# greenhousectrl-latest.net
KiCad netlist of a schematic drawn in EAGLE
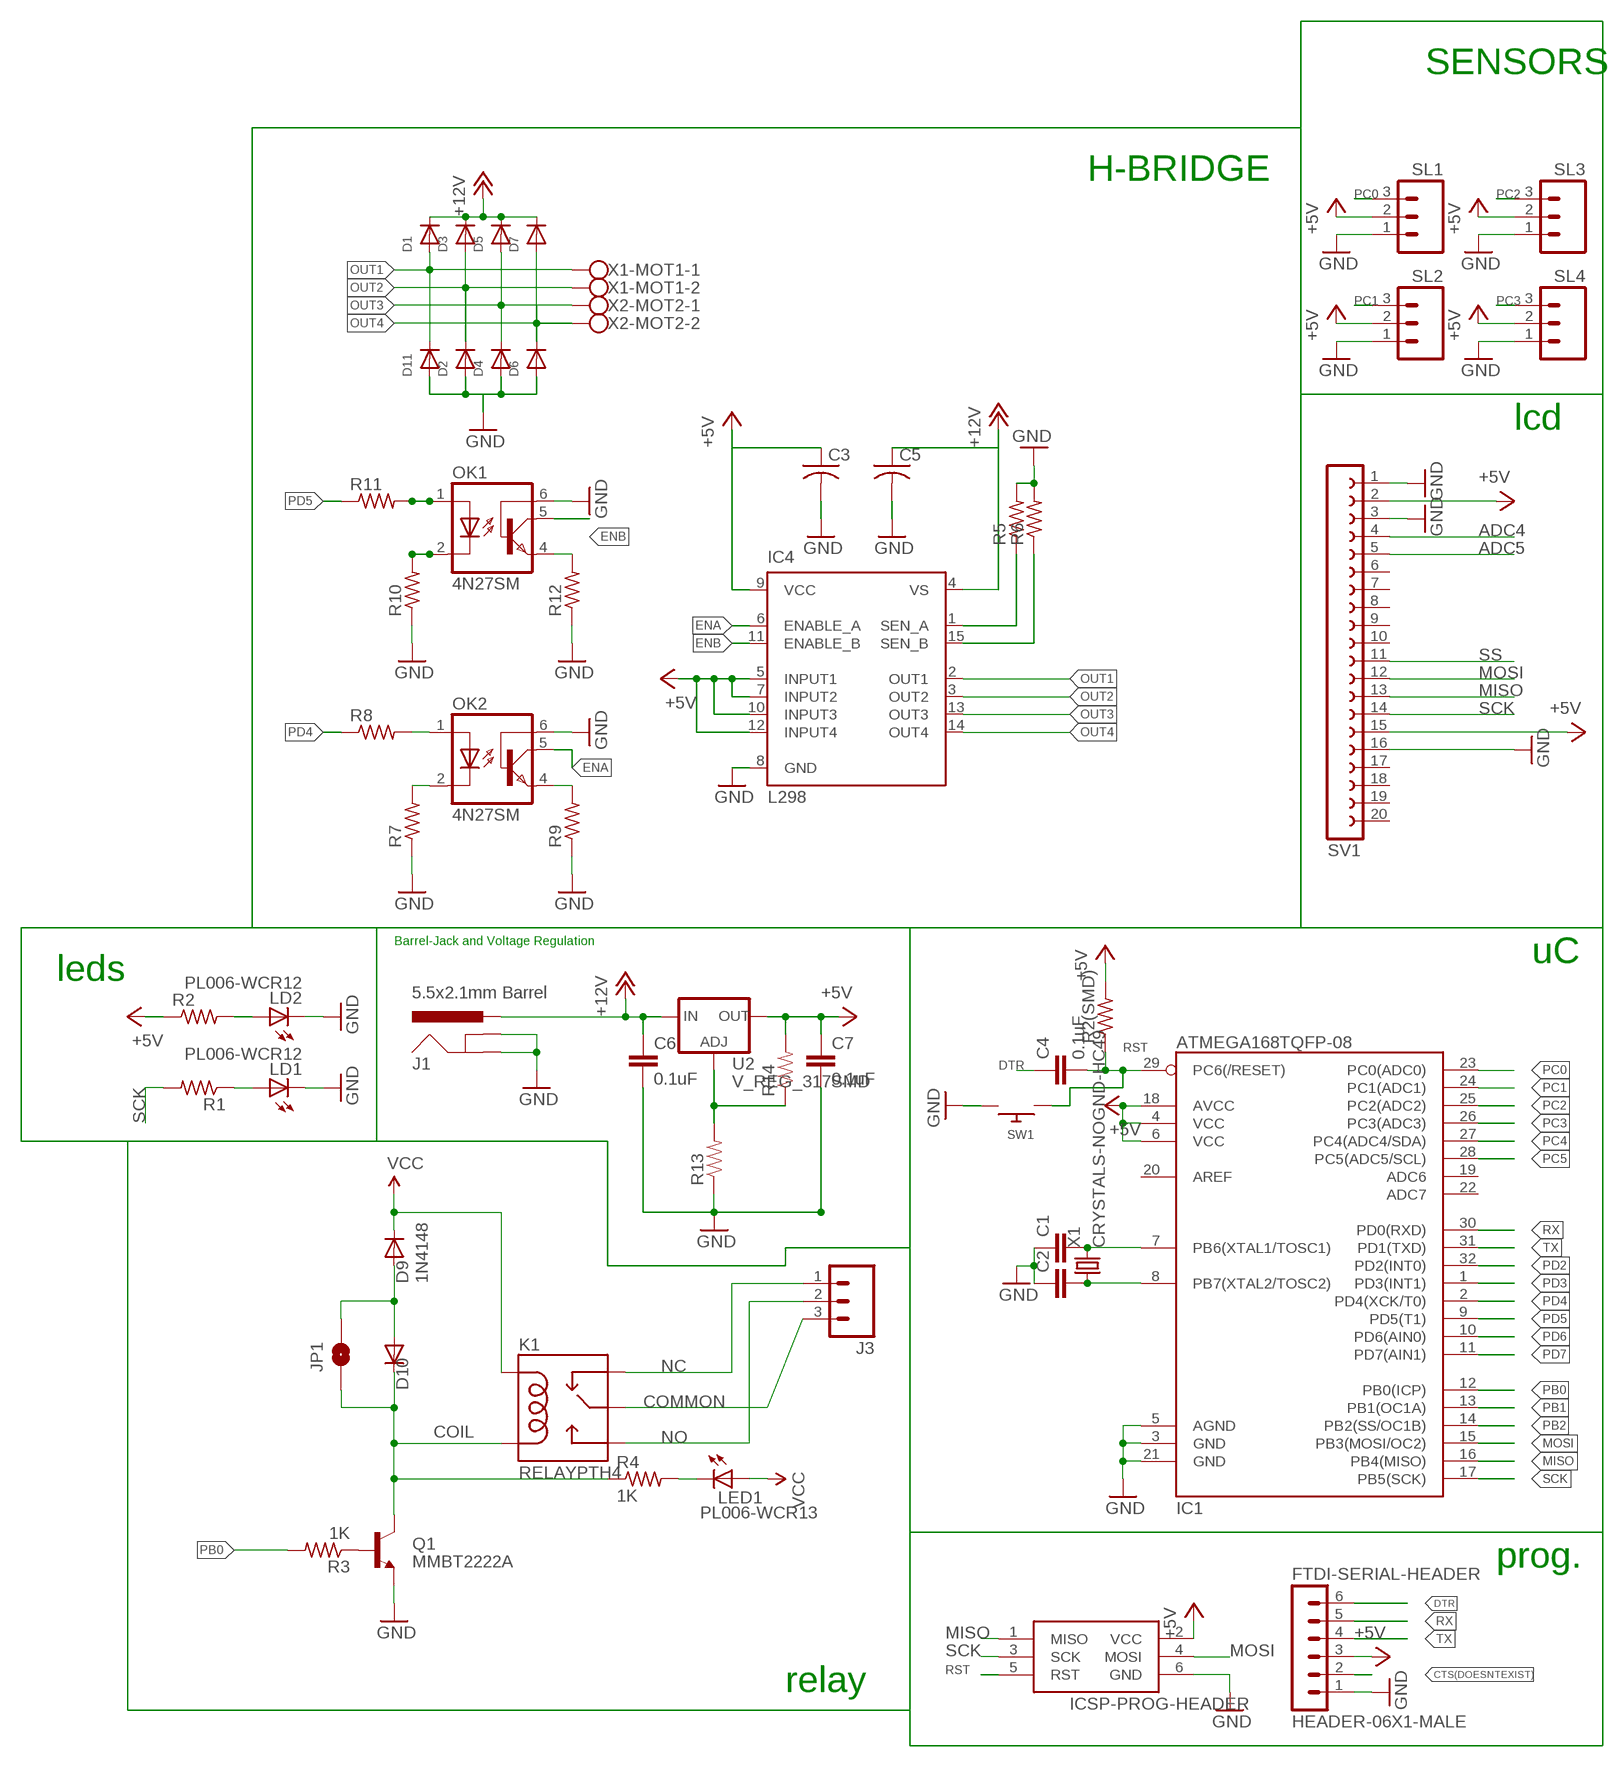
[diagram p0: schematic, sheet 1]

(export (version "E")
  (design (tool "Eeschema 10.0.6"))
  (components
    (comp (ref "C1")
      (value "C-EUC0805")
      (footprint "eagle-import:C0805")
      (libsource (lib "eagle-import") (part "C-EUC0805"))
    )
    (comp (ref "C2")
      (value "C-EUC0805")
      (footprint "eagle-import:C0805")
      (libsource (lib "eagle-import") (part "C-EUC0805"))
    )
    (comp (ref "C3")
      (value "C-US025-024X044")
      (footprint "eagle-import:C025-024X044")
      (libsource (lib "eagle-import") (part "C-US025-024X044"))
    )
    (comp (ref "C4")
      (value "0.1uF")
      (footprint "eagle-import:0603-CAP")
      (libsource (lib "eagle-import") (part "0.1UF-25V(+80/-20%)(0603)"))
    )
    (comp (ref "C5")
      (value "C-US025-024X044")
      (footprint "eagle-import:C025-024X044")
      (libsource (lib "eagle-import") (part "C-US025-024X044"))
    )
    (comp (ref "C6")
      (value "0.1uF")
      (footprint "eagle-import:0603-CAP")
      (libsource (lib "eagle-import") (part "0.1UF-25V(+80/-20%)(0603)"))
    )
    (comp (ref "C7")
      (value "0.1uF")
      (footprint "eagle-import:0603-CAP")
      (libsource (lib "eagle-import") (part "0.1UF-25V(+80/-20%)(0603)"))
    )
    (comp (ref "D1")
      (value "DIODESOD-523")
      (footprint "eagle-import:SOD-523")
      (libsource (lib "eagle-import") (part "DIODESOD-523"))
    )
    (comp (ref "D2")
      (value "DIODESOD-523")
      (footprint "eagle-import:SOD-523")
      (libsource (lib "eagle-import") (part "DIODESOD-523"))
    )
    (comp (ref "D3")
      (value "DIODESOD-523")
      (footprint "eagle-import:SOD-523")
      (libsource (lib "eagle-import") (part "DIODESOD-523"))
    )
    (comp (ref "D4")
      (value "DIODESOD-523")
      (footprint "eagle-import:SOD-523")
      (libsource (lib "eagle-import") (part "DIODESOD-523"))
    )
    (comp (ref "D5")
      (value "DIODESOD-523")
      (footprint "eagle-import:SOD-523")
      (libsource (lib "eagle-import") (part "DIODESOD-523"))
    )
    (comp (ref "D6")
      (value "DIODESOD-523")
      (footprint "eagle-import:SOD-523")
      (libsource (lib "eagle-import") (part "DIODESOD-523"))
    )
    (comp (ref "D7")
      (value "DIODESOD-523")
      (footprint "eagle-import:SOD-523")
      (libsource (lib "eagle-import") (part "DIODESOD-523"))
    )
    (comp (ref "D9")
      (value "1N4148")
      (footprint "eagle-import:SOD-323F")
      (libsource (lib "eagle-import") (part "DIODESOD-323F"))
    )
    (comp (ref "D10")
      (value "Zener")
      (footprint "eagle-import:SOD-323F")
      (libsource (lib "eagle-import") (part "DIODESOD-323F"))
    )
    (comp (ref "D11")
      (value "DIODESOD-523")
      (footprint "eagle-import:SOD-523")
      (libsource (lib "eagle-import") (part "DIODESOD-523"))
    )
    (comp (ref "FTDI-SERIAL-HEADER")
      (value "HEADER-06X1-MALE")
      (footprint "eagle-import:06X1-PTH")
      (libsource (lib "eagle-import") (part "HEADER-06X1?-MALE"))
    )
    (comp (ref "IC1")
      (value "ATMEGA168TQFP-08")
      (footprint "eagle-import:TQFP32-08")
      (libsource (lib "eagle-import") (part "ATMEGA168TQFP-08"))
    )
    (comp (ref "IC4")
      (value "L298")
      (footprint "eagle-import:MULTIWATT-15")
      (fields (field (name "MPN") "L298N"))
      (libsource (lib "eagle-import") (part "L298"))
    )
    (comp (ref "ICSP-PROG-HEADER")
      (value "AVRISP-6")
      (footprint "eagle-import:AVRISP")
      (libsource (lib "eagle-import") (part "AVRISP-6"))
    )
    (comp (ref "J1")
      (value "5.5x2.1mm Barrel")
      (footprint "eagle-import:POWER_JACK_SMD")
      (libsource (lib "eagle-import") (part "POWER_JACKSMD"))
    )
    (comp (ref "J3")
      (value "M03-SCREW-5MM")
      (footprint "eagle-import:SCREWTERMINAL-5MM-3")
      (libsource (lib "eagle-import") (part "M03-SCREW-5MM"))
    )
    (comp (ref "JP1")
      (value "JUMPER-PAD-2-NOYES_SILK")
      (footprint "eagle-import:PAD-JUMPER-2-NO_YES_SILK")
      (libsource (lib "eagle-import") (part "JUMPER-PAD-2-NOYES_SILK"))
    )
    (comp (ref "K1")
      (value "RELAYPTH4")
      (footprint "eagle-import:RELAY-JZC")
      (libsource (lib "eagle-import") (part "RELAYPTH4"))
    )
    (comp (ref "LD1")
      (value "PL006-WCR12")
      (footprint "eagle-import:SOT23")
      (libsource (lib "eagle-import") (part "PL006-WCR12"))
    )
    (comp (ref "LD2")
      (value "PL006-WCR12")
      (footprint "eagle-import:SOT23")
      (libsource (lib "eagle-import") (part "PL006-WCR12"))
    )
    (comp (ref "LED1")
      (value "PL006-WCR13")
      (footprint "eagle-import:SOT23")
      (fields (field (name "PROD_ID") "DIO-09529"))
      (libsource (lib "eagle-import") (part "PL006-WCR13"))
    )
    (comp (ref "OK1")
      (value "4N27SM")
      (footprint "eagle-import:DIL6-SMD")
      (fields (field (name "MF") "FAIRCHILD SEMICONDUCTOR") (field (name "MPN") "4N27S-M"))
      (libsource (lib "eagle-import") (part "4N?MS27"))
    )
    (comp (ref "OK2")
      (value "4N27SM")
      (footprint "eagle-import:DIL6-SMD")
      (fields (field (name "MF") "FAIRCHILD SEMICONDUCTOR") (field (name "MPN") "4N27S-M"))
      (libsource (lib "eagle-import") (part "4N?MS27"))
    )
    (comp (ref "Q1")
      (value "MMBT2222A")
      (footprint "eagle-import:SOT23-3")
      (libsource (lib "eagle-import") (part "TRANSISTOR_NPNMMBT2222A"))
    )
    (comp (ref "R1")
      (value "R-US_M0805")
      (footprint "eagle-import:M0805")
      (libsource (lib "eagle-import") (part "R-US_M0805"))
    )
    (comp (ref "R2")
      (value "R-US_M0805")
      (footprint "eagle-import:M0805")
      (libsource (lib "eagle-import") (part "R-US_M0805"))
    )
    (comp (ref "R2(SMD)")
      (value "R-US_M0805")
      (footprint "eagle-import:M0805")
      (libsource (lib "eagle-import") (part "R-US_M0805"))
    )
    (comp (ref "R3")
      (value "1K")
      (footprint "eagle-import:M0805")
      (libsource (lib "eagle-import") (part "R-US_M0805"))
    )
    (comp (ref "R4")
      (value "1K")
      (footprint "eagle-import:M0805")
      (libsource (lib "eagle-import") (part "R-US_M0805"))
    )
    (comp (ref "R5")
      (value "R-US_M0805")
      (footprint "eagle-import:M0805")
      (libsource (lib "eagle-import") (part "R-US_M0805"))
    )
    (comp (ref "R6")
      (value "R-US_M0805")
      (footprint "eagle-import:M0805")
      (libsource (lib "eagle-import") (part "R-US_M0805"))
    )
    (comp (ref "R7")
      (value "R-US_M0805")
      (footprint "eagle-import:M0805")
      (libsource (lib "eagle-import") (part "R-US_M0805"))
    )
    (comp (ref "R8")
      (value "R-US_M0805")
      (footprint "eagle-import:M0805")
      (libsource (lib "eagle-import") (part "R-US_M0805"))
    )
    (comp (ref "R9")
      (value "R-US_M0805")
      (footprint "eagle-import:M0805")
      (libsource (lib "eagle-import") (part "R-US_M0805"))
    )
    (comp (ref "R10")
      (value "R-US_M0805")
      (footprint "eagle-import:M0805")
      (libsource (lib "eagle-import") (part "R-US_M0805"))
    )
    (comp (ref "R11")
      (value "R-US_M0805")
      (footprint "eagle-import:M0805")
      (libsource (lib "eagle-import") (part "R-US_M0805"))
    )
    (comp (ref "R12")
      (value "R-US_M0805")
      (footprint "eagle-import:M0805")
      (libsource (lib "eagle-import") (part "R-US_M0805"))
    )
    (comp (ref "R13")
      (value "RESISTOR0402")
      (footprint "eagle-import:0402-RES")
      (libsource (lib "eagle-import") (part "RESISTOR0402"))
    )
    (comp (ref "R14")
      (value "RESISTOR0402")
      (footprint "eagle-import:0402-RES")
      (libsource (lib "eagle-import") (part "RESISTOR0402"))
    )
    (comp (ref "SL1")
      (value "M03")
      (footprint "eagle-import:03P")
      (libsource (lib "eagle-import") (part "M03"))
    )
    (comp (ref "SL2")
      (value "M03")
      (footprint "eagle-import:03P")
      (libsource (lib "eagle-import") (part "M03"))
    )
    (comp (ref "SL3")
      (value "M03")
      (footprint "eagle-import:03P")
      (libsource (lib "eagle-import") (part "M03"))
    )
    (comp (ref "SL4")
      (value "M03")
      (footprint "eagle-import:03P")
      (libsource (lib "eagle-import") (part "M03"))
    )
    (comp (ref "SV1")
      (value "FE20-1")
      (footprint "eagle-import:FE20")
      (libsource (lib "eagle-import") (part "FE20-1"))
    )
    (comp (ref "SW1")
      (value "SWITCH_PUSHBUTTONC&K_KSS")
      (footprint "eagle-import:BTN_CK_KSS")
      (libsource (lib "eagle-import") (part "SWITCH_PUSHBUTTONC&K_KSS"))
    )
    (comp (ref "U2")
      (value "V_REG_317SMD")
      (footprint "eagle-import:SOT223")
      (libsource (lib "eagle-import") (part "V_REG_317SMD"))
    )
    (comp (ref "X1")
      (value "CRYSTALS-NOGND-HC49")
      (footprint "eagle-import:HC49")
      (libsource (lib "eagle-import") (part "CRYSTALS-NOGND-HC49"))
    )
    (comp (ref "X1-MOT1")
      (value "W237-102")
      (footprint "eagle-import:W237-102")
      (fields (field (name "MPN") "237-102"))
      (libsource (lib "eagle-import") (part "W237-102"))
    )
    (comp (ref "X2-MOT2")
      (value "W237-102")
      (footprint "eagle-import:W237-102")
      (fields (field (name "MPN") "237-102"))
      (libsource (lib "eagle-import") (part "W237-102"))
    )
  )
  (nets
    (net (code "1") (name "+5V") (class "Default")
      (node (ref "C3") (pin "1") (pinfunction "1_1") (pintype "passive"))
      (node (ref "C7") (pin "1") (pinfunction "1_1") (pintype "passive"))
      (node (ref "FTDI-SERIAL-HEADER") (pin "3") (pinfunction "3_3") (pintype "passive"))
      (node (ref "IC1") (pin "18") (pinfunction "AVCC_18") (pintype "bidirectional"))
      (node (ref "IC1") (pin "4") (pinfunction "VCC_4") (pintype "bidirectional"))
      (node (ref "IC1") (pin "6") (pinfunction "VCC_6") (pintype "bidirectional"))
      (node (ref "IC4") (pin "10") (pinfunction "INPUT3_10") (pintype "input"))
      (node (ref "IC4") (pin "12") (pinfunction "INPUT4_12") (pintype "input"))
      (node (ref "IC4") (pin "5") (pinfunction "INPUT1_5") (pintype "input"))
      (node (ref "IC4") (pin "7") (pinfunction "INPUT2_7") (pintype "input"))
      (node (ref "IC4") (pin "9") (pinfunction "VCC_9") (pintype "power_in"))
      (node (ref "ICSP-PROG-HEADER") (pin "2") (pinfunction "VCC_2") (pintype "power_in"))
      (node (ref "R14") (pin "2") (pinfunction "2_2") (pintype "passive"))
      (node (ref "R2") (pin "1") (pinfunction "1_1") (pintype "passive"))
      (node (ref "R2(SMD)") (pin "2") (pinfunction "2_2") (pintype "passive"))
      (node (ref "SL1") (pin "2") (pinfunction "2_2") (pintype "passive"))
      (node (ref "SL2") (pin "2") (pinfunction "2_2") (pintype "passive"))
      (node (ref "SL3") (pin "2") (pinfunction "2_2") (pintype "passive"))
      (node (ref "SL4") (pin "2") (pinfunction "2_2") (pintype "passive"))
      (node (ref "SV1") (pin "15") (pinfunction "15_15") (pintype "passive"))
      (node (ref "SV1") (pin "2") (pinfunction "2_2") (pintype "passive"))
      (node (ref "U2") (pin "2") (pinfunction "OUT_2") (pintype "output"))
    )
    (net (code "2") (name "+12V") (class "Default")
      (node (ref "C5") (pin "1") (pinfunction "1_1") (pintype "passive"))
      (node (ref "C6") (pin "1") (pinfunction "1_1") (pintype "passive"))
      (node (ref "D1") (pin "K") (pinfunction "C_K") (pintype "passive"))
      (node (ref "D3") (pin "K") (pinfunction "C_K") (pintype "passive"))
      (node (ref "D5") (pin "K") (pinfunction "C_K") (pintype "passive"))
      (node (ref "D7") (pin "K") (pinfunction "C_K") (pintype "passive"))
      (node (ref "IC4") (pin "4") (pinfunction "VS_4") (pintype "power_in"))
      (node (ref "J1") (pin "VIN0") (pinfunction "PWR_VIN0") (pintype "bidirectional"))
      (node (ref "U2") (pin "3") (pinfunction "IN_3") (pintype "input"))
    )
    (net (code "3") (name "/ADC4") (class "Default")
      (node (ref "SV1") (pin "4") (pinfunction "4_4") (pintype "passive"))
    )
    (net (code "4") (name "/ADC5") (class "Default")
      (node (ref "SV1") (pin "5") (pinfunction "5_5") (pintype "passive"))
    )
    (net (code "5") (name "/COIL") (class "Default")
      (node (ref "D10") (pin "C") (pinfunction "C_C") (pintype "passive"))
      (node (ref "JP1") (pin "1") (pinfunction "1_1") (pintype "passive"))
      (node (ref "K1") (pin "1") (pinfunction "COIL2_1") (pintype "bidirectional"))
      (node (ref "Q1") (pin "3") (pinfunction "C_3") (pintype "passive"))
      (node (ref "R4") (pin "1") (pinfunction "1_1") (pintype "passive"))
    )
    (net (code "6") (name "/COMMON") (class "Default")
      (node (ref "J3") (pin "3") (pinfunction "3_3") (pintype "passive"))
      (node (ref "K1") (pin "4") (pinfunction "MAIN_4") (pintype "bidirectional"))
    )
    (net (code "7") (name "/NC") (class "Default")
      (node (ref "J3") (pin "1") (pinfunction "1_1") (pintype "passive"))
      (node (ref "K1") (pin "2") (pinfunction "NC_2") (pintype "bidirectional"))
    )
    (net (code "8") (name "/NO") (class "Default")
      (node (ref "J3") (pin "2") (pinfunction "2_2") (pintype "passive"))
      (node (ref "K1") (pin "3") (pinfunction "NO_3") (pintype "bidirectional"))
    )
    (net (code "9") (name "/RST") (class "Default")
      (node (ref "C4") (pin "2") (pinfunction "2_2") (pintype "passive"))
      (node (ref "IC1") (pin "29") (pinfunction "PC6(/RESET)_29") (pintype "bidirectional"))
      (node (ref "ICSP-PROG-HEADER") (pin "5") (pinfunction "RST_5") (pintype "output"))
      (node (ref "R2(SMD)") (pin "1") (pinfunction "1_1") (pintype "passive"))
      (node (ref "SW1") (pin "P$1") (pinfunction "P$1_P$1") (pintype "passive"))
    )
    (net (code "10") (name "/SS") (class "Default")
      (node (ref "SV1") (pin "11") (pinfunction "11_11") (pintype "passive"))
    )
    (net (code "11") (name "CTS(DOESNTEXIST)") (class "Default")
      (node (ref "FTDI-SERIAL-HEADER") (pin "2") (pinfunction "2_2") (pintype "passive"))
    )
    (net (code "12") (name "DTR") (class "Default")
      (node (ref "C4") (pin "1") (pinfunction "1_1") (pintype "passive"))
      (node (ref "FTDI-SERIAL-HEADER") (pin "6") (pinfunction "6_6") (pintype "passive"))
    )
    (net (code "13") (name "ENA") (class "Default")
      (node (ref "IC4") (pin "6") (pinfunction "ENABLE_A_6") (pintype "input"))
      (node (ref "OK2") (pin "5") (pinfunction "COL_5") (pintype "passive"))
    )
    (net (code "14") (name "ENB") (class "Default")
      (node (ref "IC4") (pin "11") (pinfunction "ENABLE_B_11") (pintype "input"))
      (node (ref "OK1") (pin "5") (pinfunction "COL_5") (pintype "passive"))
    )
    (net (code "15") (name "GND") (class "Default")
      (node (ref "C1") (pin "1") (pinfunction "1_1") (pintype "passive"))
      (node (ref "C2") (pin "1") (pinfunction "1_1") (pintype "passive"))
      (node (ref "C3") (pin "2") (pinfunction "2_2") (pintype "passive"))
      (node (ref "C5") (pin "2") (pinfunction "2_2") (pintype "passive"))
      (node (ref "C6") (pin "2") (pinfunction "2_2") (pintype "passive"))
      (node (ref "C7") (pin "2") (pinfunction "2_2") (pintype "passive"))
      (node (ref "D11") (pin "A") (pinfunction "A_A") (pintype "passive"))
      (node (ref "D2") (pin "A") (pinfunction "A_A") (pintype "passive"))
      (node (ref "D4") (pin "A") (pinfunction "A_A") (pintype "passive"))
      (node (ref "D6") (pin "A") (pinfunction "A_A") (pintype "passive"))
      (node (ref "FTDI-SERIAL-HEADER") (pin "1") (pinfunction "1_1") (pintype "passive"))
      (node (ref "IC1") (pin "21") (pinfunction "GND_21") (pintype "bidirectional"))
      (node (ref "IC1") (pin "3") (pinfunction "GND_3") (pintype "bidirectional"))
      (node (ref "IC1") (pin "5") (pinfunction "AGND_5") (pintype "bidirectional"))
      (node (ref "IC4") (pin "8") (pinfunction "GND_8") (pintype "power_in"))
      (node (ref "ICSP-PROG-HEADER") (pin "6") (pinfunction "GND_6") (pintype "power_in"))
      (node (ref "J1") (pin "GND") (pinfunction "GNDBREAK_GND") (pintype "bidirectional"))
      (node (ref "J1") (pin "P$4") (pinfunction "GND_P$4") (pintype "bidirectional"))
      (node (ref "LD1") (pin "3") (pinfunction "C_3") (pintype "passive"))
      (node (ref "LD2") (pin "3") (pinfunction "C_3") (pintype "passive"))
      (node (ref "OK1") (pin "6") (pinfunction "BAS_6") (pintype "passive"))
      (node (ref "OK2") (pin "6") (pinfunction "BAS_6") (pintype "passive"))
      (node (ref "Q1") (pin "2") (pinfunction "E_2") (pintype "passive"))
      (node (ref "R10") (pin "1") (pinfunction "1_1") (pintype "passive"))
      (node (ref "R12") (pin "1") (pinfunction "1_1") (pintype "passive"))
      (node (ref "R13") (pin "1") (pinfunction "1_1") (pintype "passive"))
      (node (ref "R5") (pin "2") (pinfunction "2_2") (pintype "passive"))
      (node (ref "R6") (pin "2") (pinfunction "2_2") (pintype "passive"))
      (node (ref "R7") (pin "1") (pinfunction "1_1") (pintype "passive"))
      (node (ref "R9") (pin "1") (pinfunction "1_1") (pintype "passive"))
      (node (ref "SL1") (pin "1") (pinfunction "1_1") (pintype "passive"))
      (node (ref "SL2") (pin "1") (pinfunction "1_1") (pintype "passive"))
      (node (ref "SL3") (pin "1") (pinfunction "1_1") (pintype "passive"))
      (node (ref "SL4") (pin "1") (pinfunction "1_1") (pintype "passive"))
      (node (ref "SV1") (pin "1") (pinfunction "1_1") (pintype "passive"))
      (node (ref "SV1") (pin "16") (pinfunction "16_16") (pintype "passive"))
      (node (ref "SV1") (pin "3") (pinfunction "3_3") (pintype "passive"))
      (node (ref "SW1") (pin "P$2") (pinfunction "P$2_P$2") (pintype "passive"))
    )
    (net (code "16") (name "MISO") (class "Default")
      (node (ref "IC1") (pin "16") (pinfunction "PB4(MISO)_16") (pintype "bidirectional"))
      (node (ref "ICSP-PROG-HEADER") (pin "1") (pinfunction "MISO_1") (pintype "input"))
      (node (ref "SV1") (pin "13") (pinfunction "13_13") (pintype "passive"))
    )
    (net (code "17") (name "MOSI") (class "Default")
      (node (ref "IC1") (pin "15") (pinfunction "PB3(MOSI/OC2)_15") (pintype "bidirectional"))
      (node (ref "ICSP-PROG-HEADER") (pin "4") (pinfunction "MOSI_4") (pintype "output"))
      (node (ref "SV1") (pin "12") (pinfunction "12_12") (pintype "passive"))
    )
    (net (code "18") (name "Net-(D10-PadA)") (class "Default")
      (node (ref "D10") (pin "A") (pinfunction "A_A") (pintype "passive"))
      (node (ref "D9") (pin "A") (pinfunction "A_A") (pintype "passive"))
      (node (ref "JP1") (pin "2") (pinfunction "2_2") (pintype "passive"))
    )
    (net (code "19") (name "Net-(IC1-PB6(XTAL1{slash}TOSC1))") (class "Default")
      (node (ref "C1") (pin "2") (pinfunction "2_2") (pintype "passive"))
      (node (ref "IC1") (pin "7") (pinfunction "PB6(XTAL1/TOSC1)_7") (pintype "bidirectional"))
      (node (ref "X1") (pin "2") (pinfunction "2_2") (pintype "passive"))
    )
    (net (code "20") (name "Net-(IC1-PB7(XTAL2{slash}TOSC2))") (class "Default")
      (node (ref "C2") (pin "2") (pinfunction "2_2") (pintype "passive"))
      (node (ref "IC1") (pin "8") (pinfunction "PB7(XTAL2/TOSC2)_8") (pintype "bidirectional"))
      (node (ref "X1") (pin "1") (pinfunction "1_1") (pintype "passive"))
    )
    (net (code "21") (name "Net-(IC4-SEN_A)") (class "Default")
      (node (ref "IC4") (pin "1") (pinfunction "SEN_A_1") (pintype "input"))
      (node (ref "R5") (pin "1") (pinfunction "1_1") (pintype "passive"))
    )
    (net (code "22") (name "Net-(IC4-SEN_B)") (class "Default")
      (node (ref "IC4") (pin "15") (pinfunction "SEN_B_15") (pintype "input"))
      (node (ref "R6") (pin "1") (pinfunction "1_1") (pintype "passive"))
    )
    (net (code "23") (name "Net-(LD1-A)") (class "Default")
      (node (ref "LD1") (pin "1") (pinfunction "A_1") (pintype "passive"))
      (node (ref "R1") (pin "1") (pinfunction "1_1") (pintype "passive"))
    )
    (net (code "24") (name "Net-(LD2-A)") (class "Default")
      (node (ref "LD2") (pin "1") (pinfunction "A_1") (pintype "passive"))
      (node (ref "R2") (pin "2") (pinfunction "2_2") (pintype "passive"))
    )
    (net (code "25") (name "Net-(LED1-C)") (class "Default")
      (node (ref "LED1") (pin "3") (pinfunction "C_3") (pintype "passive"))
      (node (ref "R4") (pin "2") (pinfunction "2_2") (pintype "passive"))
    )
    (net (code "26") (name "Net-(OK1-A)") (class "Default")
      (node (ref "OK1") (pin "1") (pinfunction "A_1") (pintype "passive"))
      (node (ref "R11") (pin "2") (pinfunction "2_2") (pintype "passive"))
    )
    (net (code "27") (name "Net-(OK1-C)") (class "Default")
      (node (ref "OK1") (pin "2") (pinfunction "C_2") (pintype "passive"))
      (node (ref "R10") (pin "2") (pinfunction "2_2") (pintype "passive"))
    )
    (net (code "28") (name "Net-(OK1-EMI)") (class "Default")
      (node (ref "OK1") (pin "4") (pinfunction "EMI_4") (pintype "passive"))
      (node (ref "R12") (pin "2") (pinfunction "2_2") (pintype "passive"))
    )
    (net (code "29") (name "Net-(OK2-A)") (class "Default")
      (node (ref "OK2") (pin "1") (pinfunction "A_1") (pintype "passive"))
      (node (ref "R8") (pin "2") (pinfunction "2_2") (pintype "passive"))
    )
    (net (code "30") (name "Net-(OK2-C)") (class "Default")
      (node (ref "OK2") (pin "2") (pinfunction "C_2") (pintype "passive"))
      (node (ref "R7") (pin "2") (pinfunction "2_2") (pintype "passive"))
    )
    (net (code "31") (name "Net-(OK2-EMI)") (class "Default")
      (node (ref "OK2") (pin "4") (pinfunction "EMI_4") (pintype "passive"))
      (node (ref "R9") (pin "2") (pinfunction "2_2") (pintype "passive"))
    )
    (net (code "32") (name "Net-(Q1-B)") (class "Default")
      (node (ref "Q1") (pin "1") (pinfunction "B_1") (pintype "passive"))
      (node (ref "R3") (pin "1") (pinfunction "1_1") (pintype "passive"))
    )
    (net (code "33") (name "Net-(U2-ADJ)") (class "Default")
      (node (ref "R13") (pin "2") (pinfunction "2_2") (pintype "passive"))
      (node (ref "R14") (pin "1") (pinfunction "1_1") (pintype "passive"))
      (node (ref "U2") (pin "1") (pinfunction "ADJ_1") (pintype "input"))
    )
    (net (code "34") (name "OUT1") (class "Default")
      (node (ref "D1") (pin "A") (pinfunction "A_A") (pintype "passive"))
      (node (ref "D11") (pin "K") (pinfunction "C_K") (pintype "passive"))
      (node (ref "IC4") (pin "2") (pinfunction "OUT1_2") (pintype "output"))
      (node (ref "X1-MOT1") (pin "1") (pinfunction "KL_1") (pintype "passive"))
    )
    (net (code "35") (name "OUT2") (class "Default")
      (node (ref "D2") (pin "K") (pinfunction "C_K") (pintype "passive"))
      (node (ref "D3") (pin "A") (pinfunction "A_A") (pintype "passive"))
      (node (ref "IC4") (pin "3") (pinfunction "OUT2_3") (pintype "output"))
      (node (ref "X1-MOT1") (pin "2") (pinfunction "KL_2") (pintype "passive"))
    )
    (net (code "36") (name "OUT3") (class "Default")
      (node (ref "D4") (pin "K") (pinfunction "C_K") (pintype "passive"))
      (node (ref "D5") (pin "A") (pinfunction "A_A") (pintype "passive"))
      (node (ref "IC4") (pin "13") (pinfunction "OUT3_13") (pintype "output"))
      (node (ref "X2-MOT2") (pin "1") (pinfunction "KL_1") (pintype "passive"))
    )
    (net (code "37") (name "OUT4") (class "Default")
      (node (ref "D6") (pin "K") (pinfunction "C_K") (pintype "passive"))
      (node (ref "D7") (pin "A") (pinfunction "A_A") (pintype "passive"))
      (node (ref "IC4") (pin "14") (pinfunction "OUT4_14") (pintype "output"))
      (node (ref "X2-MOT2") (pin "2") (pinfunction "KL_2") (pintype "passive"))
    )
    (net (code "38") (name "PB0") (class "Default")
      (node (ref "IC1") (pin "12") (pinfunction "PB0(ICP)_12") (pintype "bidirectional"))
      (node (ref "R3") (pin "2") (pinfunction "2_2") (pintype "passive"))
    )
    (net (code "39") (name "PB1") (class "Default")
      (node (ref "IC1") (pin "13") (pinfunction "PB1(OC1A)_13") (pintype "bidirectional"))
    )
    (net (code "40") (name "PB2") (class "Default")
      (node (ref "IC1") (pin "14") (pinfunction "PB2(SS/OC1B)_14") (pintype "bidirectional"))
    )
    (net (code "41") (name "PC0") (class "Default")
      (node (ref "IC1") (pin "23") (pinfunction "PC0(ADC0)_23") (pintype "bidirectional"))
      (node (ref "SL1") (pin "3") (pinfunction "3_3") (pintype "passive"))
    )
    (net (code "42") (name "PC1") (class "Default")
      (node (ref "IC1") (pin "24") (pinfunction "PC1(ADC1)_24") (pintype "bidirectional"))
      (node (ref "SL2") (pin "3") (pinfunction "3_3") (pintype "passive"))
    )
    (net (code "43") (name "PC2") (class "Default")
      (node (ref "IC1") (pin "25") (pinfunction "PC2(ADC2)_25") (pintype "bidirectional"))
      (node (ref "SL3") (pin "3") (pinfunction "3_3") (pintype "passive"))
    )
    (net (code "44") (name "PC3") (class "Default")
      (node (ref "IC1") (pin "26") (pinfunction "PC3(ADC3)_26") (pintype "bidirectional"))
      (node (ref "SL4") (pin "3") (pinfunction "3_3") (pintype "passive"))
    )
    (net (code "45") (name "PC4") (class "Default")
      (node (ref "IC1") (pin "27") (pinfunction "PC4(ADC4/SDA)_27") (pintype "bidirectional"))
    )
    (net (code "46") (name "PC5") (class "Default")
      (node (ref "IC1") (pin "28") (pinfunction "PC5(ADC5/SCL)_28") (pintype "bidirectional"))
    )
    (net (code "47") (name "PD2") (class "Default")
      (node (ref "IC1") (pin "32") (pinfunction "PD2(INT0)_32") (pintype "bidirectional"))
    )
    (net (code "48") (name "PD3") (class "Default")
      (node (ref "IC1") (pin "1") (pinfunction "PD3(INT1)_1") (pintype "bidirectional"))
    )
    (net (code "49") (name "PD4") (class "Default")
      (node (ref "IC1") (pin "2") (pinfunction "PD4(XCK/T0)_2") (pintype "bidirectional"))
      (node (ref "R8") (pin "1") (pinfunction "1_1") (pintype "passive"))
    )
    (net (code "50") (name "PD5") (class "Default")
      (node (ref "IC1") (pin "9") (pinfunction "PD5(T1)_9") (pintype "bidirectional"))
      (node (ref "R11") (pin "1") (pinfunction "1_1") (pintype "passive"))
    )
    (net (code "51") (name "PD6") (class "Default")
      (node (ref "IC1") (pin "10") (pinfunction "PD6(AIN0)_10") (pintype "bidirectional"))
    )
    (net (code "52") (name "PD7") (class "Default")
      (node (ref "IC1") (pin "11") (pinfunction "PD7(AIN1)_11") (pintype "bidirectional"))
    )
    (net (code "53") (name "RX") (class "Default")
      (node (ref "FTDI-SERIAL-HEADER") (pin "5") (pinfunction "5_5") (pintype "passive"))
      (node (ref "IC1") (pin "30") (pinfunction "PD0(RXD)_30") (pintype "bidirectional"))
    )
    (net (code "54") (name "SCK") (class "Default")
      (node (ref "IC1") (pin "17") (pinfunction "PB5(SCK)_17") (pintype "bidirectional"))
      (node (ref "ICSP-PROG-HEADER") (pin "3") (pinfunction "SCK_3") (pintype "output"))
      (node (ref "R1") (pin "2") (pinfunction "2_2") (pintype "passive"))
      (node (ref "SV1") (pin "14") (pinfunction "14_14") (pintype "passive"))
    )
    (net (code "55") (name "TX") (class "Default")
      (node (ref "FTDI-SERIAL-HEADER") (pin "4") (pinfunction "4_4") (pintype "passive"))
      (node (ref "IC1") (pin "31") (pinfunction "PD1(TXD)_31") (pintype "bidirectional"))
    )
    (net (code "56") (name "VCC") (class "Default")
      (node (ref "D9") (pin "C") (pinfunction "C_C") (pintype "passive"))
      (node (ref "K1") (pin "5") (pinfunction "COIL1_5") (pintype "bidirectional"))
      (node (ref "LED1") (pin "1") (pinfunction "A_1") (pintype "passive"))
    )
    (net (code "57") (name "unconnected-(IC1-ADC6-Pad19)") (class "Default")
      (node (ref "IC1") (pin "19") (pinfunction "ADC6_19") (pintype "bidirectional"))
    )
    (net (code "58") (name "unconnected-(IC1-ADC7-Pad22)") (class "Default")
      (node (ref "IC1") (pin "22") (pinfunction "ADC7_22") (pintype "bidirectional"))
    )
    (net (code "59") (name "unconnected-(IC1-AREF-Pad20)") (class "Default")
      (node (ref "IC1") (pin "20") (pinfunction "AREF_20") (pintype "bidirectional"))
    )
    (net (code "60") (name "unconnected-(SV1-Pad6)") (class "Default")
      (node (ref "SV1") (pin "6") (pinfunction "6_6") (pintype "passive"))
    )
    (net (code "61") (name "unconnected-(SV1-Pad7)") (class "Default")
      (node (ref "SV1") (pin "7") (pinfunction "7_7") (pintype "passive"))
    )
    (net (code "62") (name "unconnected-(SV1-Pad8)") (class "Default")
      (node (ref "SV1") (pin "8") (pinfunction "8_8") (pintype "passive"))
    )
    (net (code "63") (name "unconnected-(SV1-Pad9)") (class "Default")
      (node (ref "SV1") (pin "9") (pinfunction "9_9") (pintype "passive"))
    )
    (net (code "64") (name "unconnected-(SV1-Pad10)") (class "Default")
      (node (ref "SV1") (pin "10") (pinfunction "10_10") (pintype "passive"))
    )
    (net (code "65") (name "unconnected-(SV1-Pad17)") (class "Default")
      (node (ref "SV1") (pin "17") (pinfunction "17_17") (pintype "passive"))
    )
    (net (code "66") (name "unconnected-(SV1-Pad18)") (class "Default")
      (node (ref "SV1") (pin "18") (pinfunction "18_18") (pintype "passive"))
    )
    (net (code "67") (name "unconnected-(SV1-Pad19)") (class "Default")
      (node (ref "SV1") (pin "19") (pinfunction "19_19") (pintype "passive"))
    )
    (net (code "68") (name "unconnected-(SV1-Pad20)") (class "Default")
      (node (ref "SV1") (pin "20") (pinfunction "20_20") (pintype "passive"))
    )
  )
)
